# DCDCDC-R2.net
KiCad netlist of a schematic drawn in EAGLE
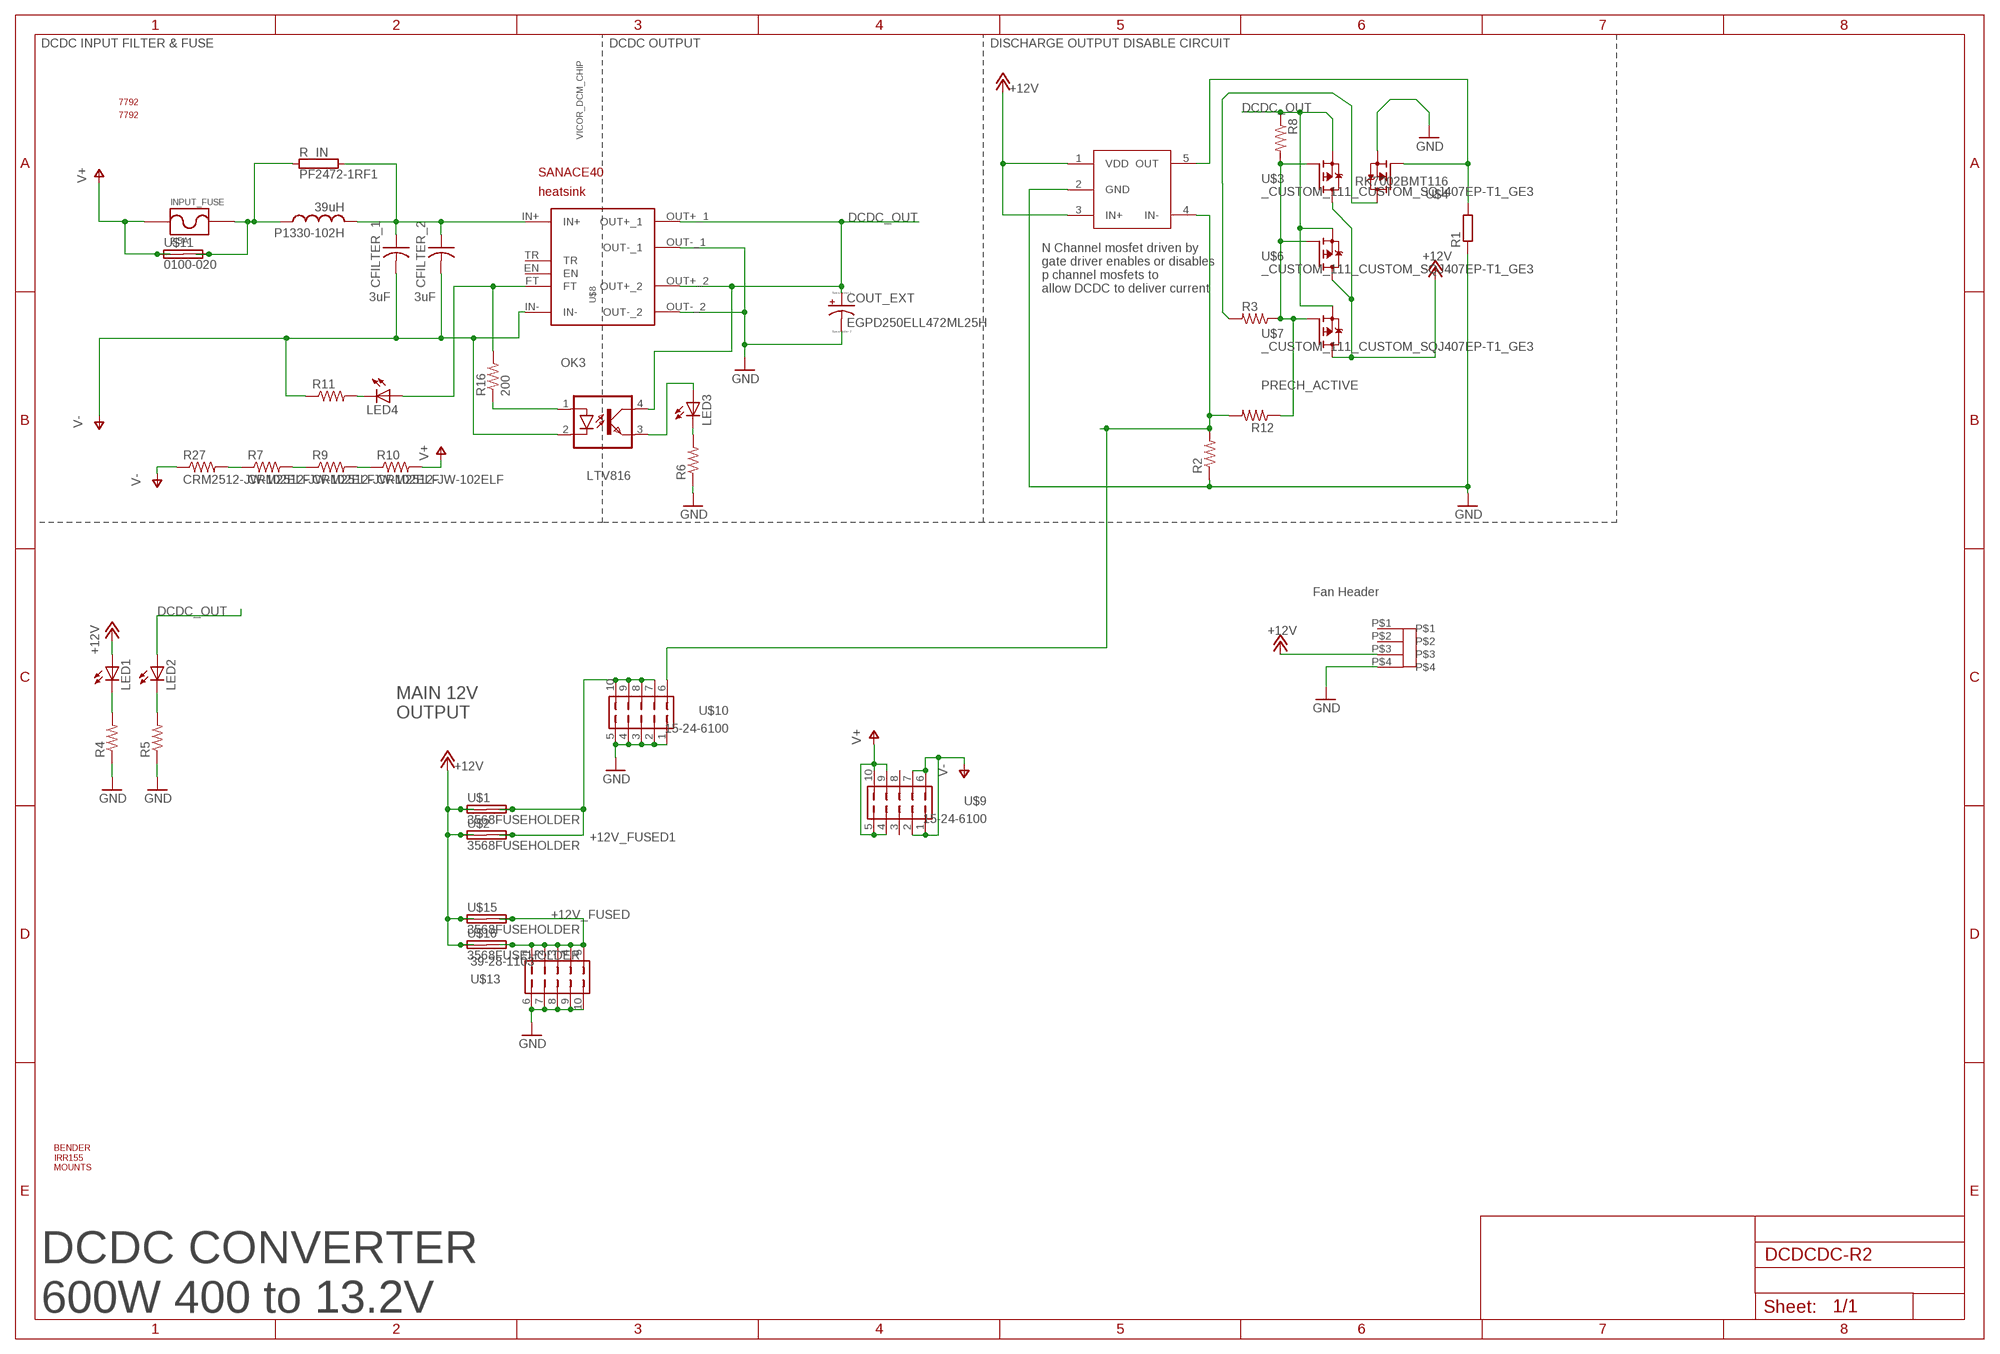
[diagram p0: schematic, sheet 1]

(export (version "E")
  (design (tool "Eeschema 10.0.6"))
  (components
    (comp (ref "CFILTER_1")
      (value "3uF")
      (footprint "eagle-import:CERALINK_FA3")
      (libsource (lib "eagle-import") (part "B58035U5305M062"))
    )
    (comp (ref "CFILTER_2")
      (value "3uF")
      (footprint "eagle-import:CERALINK_FA3")
      (libsource (lib "eagle-import") (part "B58035U5305M062"))
    )
    (comp (ref "COUT_EXT")
      (value "EGPD250ELL472ML25H")
      (footprint "eagle-import:E7,5-16")
      (libsource (lib "eagle-import") (part "CPOL-USE7.5-16"))
    )
    (comp (ref "INPUT_FUSE")
      (value "2.5A")
      (footprint "eagle-import:_CUSTOM_PARTS_LF_885")
      (libsource (lib "eagle-import") (part "_CUSTOM_PARTS_LF_885"))
    )
    (comp (ref "LED1")
      (value "LEDCHIPLED_0805")
      (footprint "eagle-import:CHIPLED_0805")
      (libsource (lib "eagle-import") (part "LEDCHIPLED_0805"))
    )
    (comp (ref "LED2")
      (value "LEDCHIPLED_0805")
      (footprint "eagle-import:CHIPLED_0805")
      (libsource (lib "eagle-import") (part "LEDCHIPLED_0805"))
    )
    (comp (ref "LED3")
      (value "LEDCHIPLED_0805")
      (footprint "eagle-import:CHIPLED_0805")
      (libsource (lib "eagle-import") (part "LEDCHIPLED_0805"))
    )
    (comp (ref "LED4")
      (value "LEDCHIPLED_0805")
      (footprint "eagle-import:CHIPLED_0805")
      (libsource (lib "eagle-import") (part "LEDCHIPLED_0805"))
    )
    (comp (ref "OK3")
      (value "LTV816")
      (footprint "eagle-import:DIL04")
      (libsource (lib "eagle-import") (part "LTV816"))
    )
    (comp (ref "P1330-102H")
      (value "39uH")
      (footprint "eagle-import:L_1510_NONSTANDARD")
      (libsource (lib "eagle-import") (part "SRP1770TA-390M"))
    )
    (comp (ref "R1")
      (value "R-EU_R0805")
      (footprint "eagle-import:R0805")
      (libsource (lib "eagle-import") (part "R-EU_R0805"))
    )
    (comp (ref "R2")
      (value "R-US_R0805")
      (footprint "eagle-import:R0805")
      (libsource (lib "eagle-import") (part "ACC-MB-R0_13324935_R-US_R0805"))
    )
    (comp (ref "R3")
      (value "R-US_R0805")
      (footprint "eagle-import:R0805")
      (libsource (lib "eagle-import") (part "ACC-MB-R0_13324935_R-US_R0805"))
    )
    (comp (ref "R4")
      (value "R-US_R0805")
      (footprint "eagle-import:R0805")
      (libsource (lib "eagle-import") (part "R-US_R0805"))
    )
    (comp (ref "R5")
      (value "R-US_R0805")
      (footprint "eagle-import:R0805")
      (libsource (lib "eagle-import") (part "R-US_R0805"))
    )
    (comp (ref "R6")
      (value "R-US_R0805")
      (footprint "eagle-import:R0805")
      (libsource (lib "eagle-import") (part "R-US_R0805"))
    )
    (comp (ref "R7")
      (value "CRM2512-JW-102ELF")
      (footprint "eagle-import:R2512")
      (libsource (lib "eagle-import") (part "R-US_R2512"))
    )
    (comp (ref "R8")
      (value "R-US_R0805")
      (footprint "eagle-import:R0805")
      (libsource (lib "eagle-import") (part "ACC-MB-R0_13324935_R-US_R0805"))
    )
    (comp (ref "R9")
      (value "CRM2512-JW-102ELF")
      (footprint "eagle-import:R2512")
      (libsource (lib "eagle-import") (part "R-US_R2512"))
    )
    (comp (ref "R10")
      (value "CRM2512-JW-102ELF")
      (footprint "eagle-import:R2512")
      (libsource (lib "eagle-import") (part "R-US_R2512"))
    )
    (comp (ref "R11")
      (value "R-US_R0805")
      (footprint "eagle-import:R0805")
      (libsource (lib "eagle-import") (part "R-US_R0805"))
    )
    (comp (ref "R12")
      (value "R-US_R0805")
      (footprint "eagle-import:R0805")
      (libsource (lib "eagle-import") (part "ACC-MB-R0_13324935_R-US_R0805"))
    )
    (comp (ref "R16")
      (value "200")
      (footprint "eagle-import:R2010")
      (libsource (lib "eagle-import") (part "Main_14107900_R-US_R2010"))
    )
    (comp (ref "R27")
      (value "CRM2512-JW-102ELF")
      (footprint "eagle-import:R2512")
      (libsource (lib "eagle-import") (part "R-US_R2512"))
    )
    (comp (ref "R_IN")
      (value "PF2472-1RF1")
      (footprint "eagle-import:TO-247-2V")
      (libsource (lib "eagle-import") (part "RMG100-V"))
    )
    (comp (ref "U$1")
      (value "3568FUSEHOLDER")
      (footprint "eagle-import:3568")
      (libsource (lib "eagle-import") (part "3568FUSEHOLDER"))
    )
    (comp (ref "U$2")
      (value "3568FUSEHOLDER")
      (footprint "eagle-import:3568")
      (libsource (lib "eagle-import") (part "3568FUSEHOLDER"))
    )
    (comp (ref "U$3")
      (value "_CUSTOM_111_CUSTOM_SQJ407EP-T1_GE3")
      (footprint "eagle-import:_CUSTOM_111_CUSTOM_TRANS_SIRA90DP-T1-GE3")
      (libsource (lib "eagle-import") (part "_CUSTOM_111_CUSTOM_SQJ407EP-T1_GE3"))
    )
    (comp (ref "U$4")
      (value "RK7002BMT116")
      (footprint "eagle-import:SOT23")
      (libsource (lib "eagle-import") (part "RK7002BMT116"))
    )
    (comp (ref "U$5")
      (value "UCC27511AQDBVRQ1")
      (footprint "eagle-import:SOT23-5L")
      (libsource (lib "eagle-import") (part "UCC27511AQDBVRQ1"))
    )
    (comp (ref "U$6")
      (value "_CUSTOM_111_CUSTOM_SQJ407EP-T1_GE3")
      (footprint "eagle-import:_CUSTOM_111_CUSTOM_TRANS_SIRA90DP-T1-GE3")
      (libsource (lib "eagle-import") (part "_CUSTOM_111_CUSTOM_SQJ407EP-T1_GE3"))
    )
    (comp (ref "U$7")
      (value "_CUSTOM_111_CUSTOM_SQJ407EP-T1_GE3")
      (footprint "eagle-import:_CUSTOM_111_CUSTOM_TRANS_SIRA90DP-T1-GE3")
      (libsource (lib "eagle-import") (part "_CUSTOM_111_CUSTOM_SQJ407EP-T1_GE3"))
    )
    (comp (ref "U$8")
      (value "VICOR_DCM_CHIP")
      (footprint "eagle-import:VICOR_CHIP_HEATSINK")
      (libsource (lib "eagle-import") (part "VICOR_DCM_CHIP"))
    )
    (comp (ref "U$9")
      (value "15-24-6100")
      (footprint "eagle-import:15-24-6100")
      (libsource (lib "eagle-import") (part "15-24-6100"))
    )
    (comp (ref "U$10")
      (value "15-24-6100")
      (footprint "eagle-import:15-24-6100")
      (libsource (lib "eagle-import") (part "15-24-6100"))
    )
    (comp (ref "U$11")
      (value "0100-020")
      (footprint "eagle-import:0100-020")
      (libsource (lib "eagle-import") (part "0100-020"))
    )
    (comp (ref "U$12")
      (value "VICOR_HEATSINK_DOUBLE")
      (footprint "eagle-import:VICOR_HEATSINK_DOUBLE")
      (libsource (lib "eagle-import") (part "VICOR_HEATSINK_DOUBLE"))
    )
    (comp (ref "U$13")
      (value "39-28-1103")
      (footprint "eagle-import:39-28-1103")
      (libsource (lib "eagle-import") (part "39-28-1103"))
    )
    (comp (ref "U$14")
      (value "7792")
      (footprint "eagle-import:7792")
      (libsource (lib "eagle-import") (part "7792"))
    )
    (comp (ref "U$15")
      (value "3568FUSEHOLDER")
      (footprint "eagle-import:3568")
      (libsource (lib "eagle-import") (part "3568FUSEHOLDER"))
    )
    (comp (ref "U$16")
      (value "3568FUSEHOLDER")
      (footprint "eagle-import:3568")
      (libsource (lib "eagle-import") (part "3568FUSEHOLDER"))
    )
    (comp (ref "U$17")
      (value "7792")
      (footprint "eagle-import:7792")
      (libsource (lib "eagle-import") (part "7792"))
    )
    (comp (ref "U$18")
      (value "9GAX0412P3S0031")
      (footprint "eagle-import:SANACE40")
      (libsource (lib "eagle-import") (part "SANACE40"))
    )
    (comp (ref "U$19")
      (value "470531000")
      (footprint "eagle-import:470531000")
      (libsource (lib "eagle-import") (part "470531000"))
    )
    (comp (ref "U$20")
      (value "BENDER_IRR155")
      (footprint "eagle-import:BENDER_IRR155")
      (libsource (lib "eagle-import") (part "BENDER_IRR155"))
    )
  )
  (nets
    (net (code "1") (name "+12V") (class "Default")
      (node (ref "LED1") (pin "A") (pinfunction "A_A") (pintype "passive"))
      (node (ref "U$1") (pin "L1") (pinfunction "1A_L1") (pintype "passive"))
      (node (ref "U$1") (pin "L2") (pinfunction "1B_L2") (pintype "passive"))
      (node (ref "U$15") (pin "L1") (pinfunction "1A_L1") (pintype "passive"))
      (node (ref "U$15") (pin "L2") (pinfunction "1B_L2") (pintype "passive"))
      (node (ref "U$16") (pin "L1") (pinfunction "1A_L1") (pintype "passive"))
      (node (ref "U$16") (pin "L2") (pinfunction "1B_L2") (pintype "passive"))
      (node (ref "U$19") (pin "P$3") (pinfunction "P$3_P$3") (pintype "bidirectional"))
      (node (ref "U$2") (pin "L1") (pinfunction "1A_L1") (pintype "passive"))
      (node (ref "U$2") (pin "L2") (pinfunction "1B_L2") (pintype "passive"))
      (node (ref "U$3") (pin "5") (pinfunction "D_5") (pintype "passive"))
      (node (ref "U$5") (pin "1") (pinfunction "VDD_1") (pintype "bidirectional"))
      (node (ref "U$5") (pin "3") (pinfunction "IN+_3") (pintype "bidirectional"))
      (node (ref "U$6") (pin "5") (pinfunction "D_5") (pintype "passive"))
      (node (ref "U$7") (pin "5") (pinfunction "D_5") (pintype "passive"))
    )
    (net (code "2") (name "/+12V_FUSED") (class "Default")
      (node (ref "U$13") (pin "1") (pinfunction "1_1") (pintype "passive"))
      (node (ref "U$13") (pin "2") (pinfunction "2_2") (pintype "passive"))
      (node (ref "U$13") (pin "3") (pinfunction "3_3") (pintype "passive"))
      (node (ref "U$13") (pin "4") (pinfunction "4_4") (pintype "passive"))
      (node (ref "U$13") (pin "5") (pinfunction "5_5") (pintype "passive"))
      (node (ref "U$15") (pin "R1") (pinfunction "2A_R1") (pintype "passive"))
      (node (ref "U$15") (pin "R2") (pinfunction "2B_R2") (pintype "passive"))
      (node (ref "U$16") (pin "R1") (pinfunction "2A_R1") (pintype "passive"))
      (node (ref "U$16") (pin "R2") (pinfunction "2B_R2") (pintype "passive"))
    )
    (net (code "3") (name "/+12V_FUSED1") (class "Default")
      (node (ref "U$1") (pin "R1") (pinfunction "2A_R1") (pintype "passive"))
      (node (ref "U$1") (pin "R2") (pinfunction "2B_R2") (pintype "passive"))
      (node (ref "U$10") (pin "10") (pinfunction "10_10") (pintype "passive"))
      (node (ref "U$10") (pin "7") (pinfunction "7_7") (pintype "passive"))
      (node (ref "U$10") (pin "8") (pinfunction "8_8") (pintype "passive"))
      (node (ref "U$10") (pin "9") (pinfunction "9_9") (pintype "passive"))
      (node (ref "U$2") (pin "R1") (pinfunction "2A_R1") (pintype "passive"))
      (node (ref "U$2") (pin "R2") (pinfunction "2B_R2") (pintype "passive"))
    )
    (net (code "4") (name "/DCDC_OUT") (class "Default")
      (node (ref "COUT_EXT") (pin "+") (pinfunction "+_+") (pintype "passive"))
      (node (ref "LED2") (pin "A") (pinfunction "A_A") (pintype "passive"))
      (node (ref "OK3") (pin "4") (pinfunction "COL_4") (pintype "passive"))
      (node (ref "R8") (pin "1") (pinfunction "1_1") (pintype "passive"))
      (node (ref "U$3") (pin "1") (pinfunction "S_1") (pintype "passive"))
      (node (ref "U$3") (pin "2") (pinfunction "S_2") (pintype "passive"))
      (node (ref "U$3") (pin "3") (pinfunction "S_3") (pintype "passive"))
      (node (ref "U$6") (pin "1") (pinfunction "S_1") (pintype "passive"))
      (node (ref "U$6") (pin "2") (pinfunction "S_2") (pintype "passive"))
      (node (ref "U$6") (pin "3") (pinfunction "S_3") (pintype "passive"))
      (node (ref "U$7") (pin "1") (pinfunction "S_1") (pintype "passive"))
      (node (ref "U$7") (pin "2") (pinfunction "S_2") (pintype "passive"))
      (node (ref "U$7") (pin "3") (pinfunction "S_3") (pintype "passive"))
      (node (ref "U$8") (pin "OUT+_1") (pinfunction "OUT+_1_OUT+_1") (pintype "bidirectional"))
      (node (ref "U$8") (pin "OUT+_2") (pinfunction "OUT+_2_OUT+_2") (pintype "bidirectional"))
    )
    (net (code "5") (name "/PRECH_ACTIVE") (class "Default")
      (node (ref "R12") (pin "2") (pinfunction "2_2") (pintype "passive"))
      (node (ref "R2") (pin "2") (pinfunction "2_2") (pintype "passive"))
      (node (ref "U$10") (pin "6") (pinfunction "6_6") (pintype "passive"))
      (node (ref "U$5") (pin "4") (pinfunction "IN-_4") (pintype "bidirectional"))
    )
    (net (code "6") (name "GND") (class "Default")
      (node (ref "COUT_EXT") (pin "-") (pinfunction "-_-") (pintype "passive"))
      (node (ref "R1") (pin "1") (pinfunction "1_1") (pintype "passive"))
      (node (ref "R2") (pin "1") (pinfunction "1_1") (pintype "passive"))
      (node (ref "R4") (pin "1") (pinfunction "1_1") (pintype "passive"))
      (node (ref "R5") (pin "1") (pinfunction "1_1") (pintype "passive"))
      (node (ref "R6") (pin "1") (pinfunction "1_1") (pintype "passive"))
      (node (ref "U$10") (pin "1") (pinfunction "1_1") (pintype "passive"))
      (node (ref "U$10") (pin "2") (pinfunction "2_2") (pintype "passive"))
      (node (ref "U$10") (pin "3") (pinfunction "3_3") (pintype "passive"))
      (node (ref "U$10") (pin "4") (pinfunction "4_4") (pintype "passive"))
      (node (ref "U$10") (pin "5") (pinfunction "5_5") (pintype "passive"))
      (node (ref "U$13") (pin "10") (pinfunction "10_10") (pintype "passive"))
      (node (ref "U$13") (pin "6") (pinfunction "6_6") (pintype "passive"))
      (node (ref "U$13") (pin "7") (pinfunction "7_7") (pintype "passive"))
      (node (ref "U$13") (pin "8") (pinfunction "8_8") (pintype "passive"))
      (node (ref "U$13") (pin "9") (pinfunction "9_9") (pintype "passive"))
      (node (ref "U$19") (pin "P$4") (pinfunction "P$4_P$4") (pintype "bidirectional"))
      (node (ref "U$4") (pin "2") (pinfunction "S_2") (pintype "passive"))
      (node (ref "U$5") (pin "2") (pinfunction "GND_2") (pintype "bidirectional"))
      (node (ref "U$8") (pin "OUT-_1") (pinfunction "OUT-_1_OUT-_1") (pintype "bidirectional"))
      (node (ref "U$8") (pin "OUT-_2") (pinfunction "OUT-_2_OUT-_2") (pintype "bidirectional"))
    )
    (net (code "7") (name "Net-(CFILTER_1-1)") (class "Default")
      (node (ref "CFILTER_1") (pin "P$1") (pinfunction "1_P$1") (pintype "passive"))
      (node (ref "CFILTER_2") (pin "P$1") (pinfunction "1_P$1") (pintype "passive"))
      (node (ref "P1330-102H") (pin "P$2") (pinfunction "2_P$2") (pintype "passive"))
      (node (ref "R_IN") (pin "2") (pinfunction "2_2") (pintype "passive"))
      (node (ref "U$8") (pin "IN+") (pinfunction "IN+_IN+") (pintype "bidirectional"))
    )
    (net (code "8") (name "Net-(LED1-PadC)") (class "Default")
      (node (ref "LED1") (pin "C") (pinfunction "C_C") (pintype "passive"))
      (node (ref "R4") (pin "2") (pinfunction "2_2") (pintype "passive"))
    )
    (net (code "9") (name "Net-(LED2-PadC)") (class "Default")
      (node (ref "LED2") (pin "C") (pinfunction "C_C") (pintype "passive"))
      (node (ref "R5") (pin "2") (pinfunction "2_2") (pintype "passive"))
    )
    (net (code "10") (name "Net-(LED3-PadC)") (class "Default")
      (node (ref "LED3") (pin "C") (pinfunction "C_C") (pintype "passive"))
      (node (ref "R6") (pin "2") (pinfunction "2_2") (pintype "passive"))
    )
    (net (code "11") (name "Net-(LED4-PadA)") (class "Default")
      (node (ref "LED4") (pin "A") (pinfunction "A_A") (pintype "passive"))
      (node (ref "R16") (pin "2") (pinfunction "2_2") (pintype "passive"))
      (node (ref "U$8") (pin "FT") (pinfunction "FT_FT") (pintype "bidirectional"))
    )
    (net (code "12") (name "Net-(LED4-PadC)") (class "Default")
      (node (ref "LED4") (pin "C") (pinfunction "C_C") (pintype "passive"))
      (node (ref "R11") (pin "2") (pinfunction "2_2") (pintype "passive"))
    )
    (net (code "13") (name "Net-(OK3-A)") (class "Default")
      (node (ref "OK3") (pin "1") (pinfunction "A_1") (pintype "passive"))
      (node (ref "R16") (pin "1") (pinfunction "1_1") (pintype "passive"))
    )
    (net (code "14") (name "Net-(OK3-EMIT)") (class "Default")
      (node (ref "LED3") (pin "A") (pinfunction "A_A") (pintype "passive"))
      (node (ref "OK3") (pin "3") (pinfunction "EMIT_3") (pintype "passive"))
    )
    (net (code "15") (name "Net-(P1330-102H-1)") (class "Default")
      (node (ref "INPUT_FUSE") (pin "P$2") (pinfunction "P$2_P$2") (pintype "bidirectional"))
      (node (ref "P1330-102H") (pin "P$1") (pinfunction "1_P$1") (pintype "passive"))
      (node (ref "R_IN") (pin "1") (pinfunction "1_1") (pintype "passive"))
      (node (ref "U$11") (pin "P$2") (pinfunction "2A_P$2") (pintype "passive"))
      (node (ref "U$11") (pin "P$4") (pinfunction "2B_P$4") (pintype "passive"))
    )
    (net (code "16") (name "Net-(R7-Pad2)") (class "Default")
      (node (ref "R7") (pin "2") (pinfunction "2_2") (pintype "passive"))
      (node (ref "R9") (pin "1") (pinfunction "1_1") (pintype "passive"))
    )
    (net (code "17") (name "Net-(R10-Pad1)") (class "Default")
      (node (ref "R10") (pin "1") (pinfunction "1_1") (pintype "passive"))
      (node (ref "R9") (pin "2") (pinfunction "2_2") (pintype "passive"))
    )
    (net (code "18") (name "Net-(R27-Pad2)") (class "Default")
      (node (ref "R27") (pin "2") (pinfunction "2_2") (pintype "passive"))
      (node (ref "R7") (pin "1") (pinfunction "1_1") (pintype "passive"))
    )
    (net (code "19") (name "Net-(U$3-G)") (class "Default")
      (node (ref "R12") (pin "1") (pinfunction "1_1") (pintype "passive"))
      (node (ref "R3") (pin "1") (pinfunction "1_1") (pintype "passive"))
      (node (ref "R8") (pin "2") (pinfunction "2_2") (pintype "passive"))
      (node (ref "U$3") (pin "4") (pinfunction "G_4") (pintype "passive"))
      (node (ref "U$6") (pin "4") (pinfunction "G_4") (pintype "passive"))
      (node (ref "U$7") (pin "4") (pinfunction "G_4") (pintype "passive"))
    )
    (net (code "20") (name "Net-(U$4-D)") (class "Default")
      (node (ref "R3") (pin "2") (pinfunction "2_2") (pintype "passive"))
      (node (ref "U$4") (pin "3") (pinfunction "D_3") (pintype "passive"))
    )
    (net (code "21") (name "Net-(U$4-G)") (class "Default")
      (node (ref "R1") (pin "2") (pinfunction "2_2") (pintype "passive"))
      (node (ref "U$4") (pin "1") (pinfunction "G_1") (pintype "passive"))
      (node (ref "U$5") (pin "5") (pinfunction "OUT_5") (pintype "bidirectional"))
    )
    (net (code "22") (name "V+") (class "Default")
      (node (ref "INPUT_FUSE") (pin "P$1") (pinfunction "P$1_P$1") (pintype "bidirectional"))
      (node (ref "R10") (pin "2") (pinfunction "2_2") (pintype "passive"))
      (node (ref "U$11") (pin "P$1") (pinfunction "1A_P$1") (pintype "passive"))
      (node (ref "U$11") (pin "P$3") (pinfunction "1B_P$3") (pintype "passive"))
      (node (ref "U$9") (pin "10") (pinfunction "10_10") (pintype "passive"))
      (node (ref "U$9") (pin "4") (pinfunction "4_4") (pintype "passive"))
      (node (ref "U$9") (pin "5") (pinfunction "5_5") (pintype "passive"))
      (node (ref "U$9") (pin "9") (pinfunction "9_9") (pintype "passive"))
    )
    (net (code "23") (name "V-") (class "Default")
      (node (ref "CFILTER_1") (pin "P$2") (pinfunction "2_P$2") (pintype "passive"))
      (node (ref "CFILTER_2") (pin "P$2") (pinfunction "2_P$2") (pintype "passive"))
      (node (ref "OK3") (pin "2") (pinfunction "C_2") (pintype "passive"))
      (node (ref "R11") (pin "1") (pinfunction "1_1") (pintype "passive"))
      (node (ref "R27") (pin "1") (pinfunction "1_1") (pintype "passive"))
      (node (ref "U$8") (pin "IN-") (pinfunction "IN-_IN-") (pintype "bidirectional"))
      (node (ref "U$9") (pin "1") (pinfunction "1_1") (pintype "passive"))
      (node (ref "U$9") (pin "2") (pinfunction "2_2") (pintype "passive"))
      (node (ref "U$9") (pin "6") (pinfunction "6_6") (pintype "passive"))
      (node (ref "U$9") (pin "7") (pinfunction "7_7") (pintype "passive"))
    )
    (net (code "24") (name "unconnected-(U$8-PadEN)") (class "Default")
      (node (ref "U$8") (pin "EN") (pinfunction "EN_EN") (pintype "bidirectional"))
    )
    (net (code "25") (name "unconnected-(U$8-PadTR)") (class "Default")
      (node (ref "U$8") (pin "TR") (pinfunction "TR_TR") (pintype "bidirectional"))
    )
    (net (code "26") (name "unconnected-(U$9-Pad3)") (class "Default")
      (node (ref "U$9") (pin "3") (pinfunction "3_3") (pintype "passive"))
    )
    (net (code "27") (name "unconnected-(U$9-Pad8)") (class "Default")
      (node (ref "U$9") (pin "8") (pinfunction "8_8") (pintype "passive"))
    )
    (net (code "28") (name "unconnected-(U$19-PadP$1)") (class "Default")
      (node (ref "U$19") (pin "P$1") (pinfunction "P$1_P$1") (pintype "bidirectional"))
    )
    (net (code "29") (name "unconnected-(U$19-PadP$2)") (class "Default")
      (node (ref "U$19") (pin "P$2") (pinfunction "P$2_P$2") (pintype "bidirectional"))
    )
  )
)
